# TP-DownHole-No2_Alternative.net
KiCad netlist of a schematic drawn in EAGLE
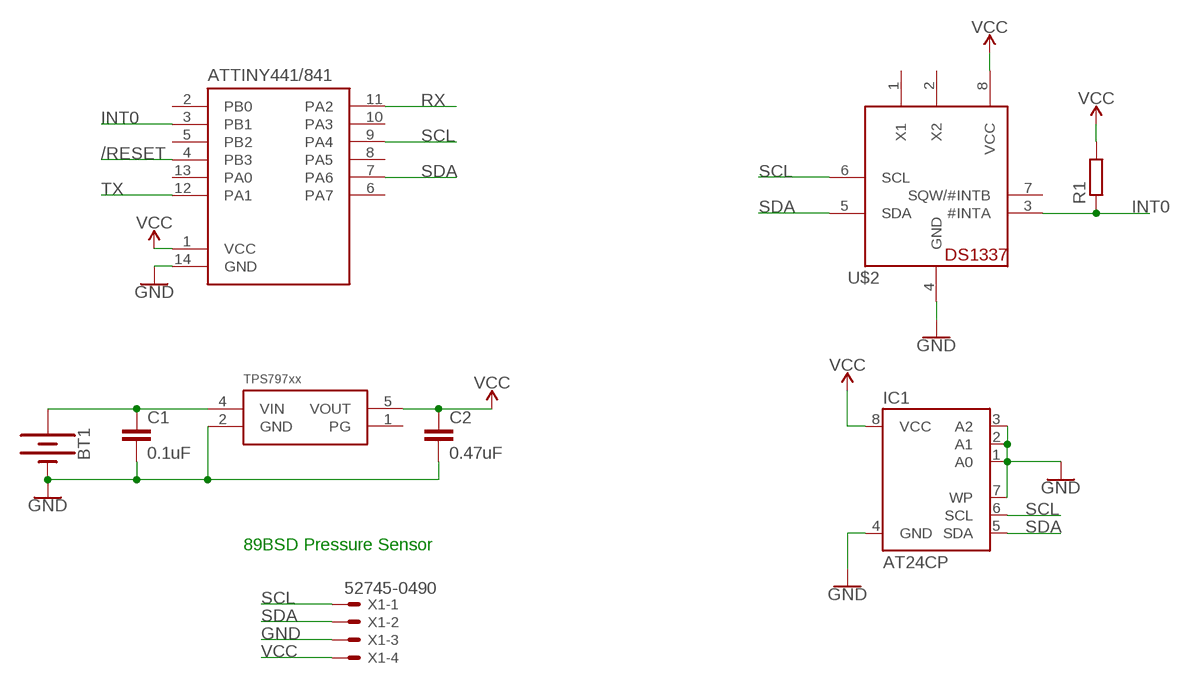
[diagram p0: schematic, sheet 1]

(export (version "E")
  (design (tool "Eeschema 10.0.6"))
  (components
    (comp (ref "BT1")
      (value "BATTERY-12MM_SMD")
      (footprint "eagle-import:BATTCON_12MM")
      (libsource (lib "eagle-import") (part "BATTERY-12MM_SMD"))
    )
    (comp (ref "C1")
      (value "0.1uF")
      (footprint "eagle-import:C0603")
      (libsource (lib "eagle-import") (part "C-EUC0603"))
    )
    (comp (ref "C2")
      (value "0.47uF")
      (footprint "eagle-import:C0603")
      (libsource (lib "eagle-import") (part "C-EUC0603"))
    )
    (comp (ref "IC1")
      (value "AT24CP")
      (footprint "eagle-import:DIL08")
      (fields (field (name "MPN") "AT24C1024BW-SH-B"))
      (libsource (lib "eagle-import") (part "AT24CP"))
    )
    (comp (ref "R1")
      (value "R-EU_R0603")
      (footprint "eagle-import:R0603")
      (libsource (lib "eagle-import") (part "R-EU_R0603"))
    )
    (comp (ref "U$1")
      (value "ATTINY441/841")
      (footprint "eagle-import:SOIC_14")
      (libsource (lib "eagle-import") (part "ATTINY441/841"))
    )
    (comp (ref "U$2")
      (value "DS1337")
      (footprint "eagle-import:DIL08-ROUND")
      (libsource (lib "eagle-import") (part "DS1337"))
    )
    (comp (ref "U$3")
      (value "TPS797XX")
      (footprint "eagle-import:DCK_R-PDSO-G5")
      (libsource (lib "eagle-import") (part "TPS797XX"))
    )
    (comp (ref "X1")
      (value "52745-0490")
      (footprint "eagle-import:52745-0490")
      (libsource (lib "eagle-import") (part "52745-0490"))
    )
  )
  (nets
    (net (code "1") (name "/INT0") (class "Default")
      (node (ref "R1") (pin "1") (pinfunction "1_1") (pintype "passive"))
      (node (ref "U$1") (pin "3") (pinfunction "PB1_3") (pintype "bidirectional"))
      (node (ref "U$2") (pin "3") (pinfunction "#INTA_3") (pintype "output"))
    )
    (net (code "2") (name "/RX") (class "Default")
      (node (ref "U$1") (pin "11") (pinfunction "PA2_11") (pintype "bidirectional"))
    )
    (net (code "3") (name "/SCL") (class "Default")
      (node (ref "IC1") (pin "6") (pinfunction "SCL_6") (pintype "bidirectional"))
      (node (ref "U$1") (pin "9") (pinfunction "PA4_9") (pintype "bidirectional"))
      (node (ref "U$2") (pin "6") (pinfunction "SCL_6") (pintype "bidirectional"))
      (node (ref "X1") (pin "1") (pinfunction "S_1") (pintype "passive"))
    )
    (net (code "4") (name "/SDA") (class "Default")
      (node (ref "IC1") (pin "5") (pinfunction "SDA_5") (pintype "bidirectional"))
      (node (ref "U$1") (pin "7") (pinfunction "PA6_7") (pintype "bidirectional"))
      (node (ref "U$2") (pin "5") (pinfunction "SDA_5") (pintype "bidirectional"))
      (node (ref "X1") (pin "2") (pinfunction "S_2") (pintype "passive"))
    )
    (net (code "5") (name "/TX") (class "Default")
      (node (ref "U$1") (pin "12") (pinfunction "PA1_12") (pintype "bidirectional"))
    )
    (net (code "6") (name "/{slash}RESET") (class "Default")
      (node (ref "U$1") (pin "4") (pinfunction "PB3_4") (pintype "bidirectional"))
    )
    (net (code "7") (name "GND") (class "Default")
      (node (ref "BT1") (pin "GND") (pinfunction "-_GND") (pintype "power_in"))
      (node (ref "C1") (pin "2") (pinfunction "2_2") (pintype "passive"))
      (node (ref "C2") (pin "2") (pinfunction "2_2") (pintype "passive"))
      (node (ref "IC1") (pin "1") (pinfunction "A0_1") (pintype "input"))
      (node (ref "IC1") (pin "2") (pinfunction "A1_2") (pintype "input"))
      (node (ref "IC1") (pin "3") (pinfunction "A2_3") (pintype "input"))
      (node (ref "IC1") (pin "4") (pinfunction "GND_4") (pintype "power_in"))
      (node (ref "IC1") (pin "7") (pinfunction "WP_7") (pintype "input"))
      (node (ref "U$1") (pin "14") (pinfunction "GND_14") (pintype "bidirectional"))
      (node (ref "U$2") (pin "4") (pinfunction "GND_4") (pintype "power_in"))
      (node (ref "U$3") (pin "2") (pinfunction "GND_2") (pintype "bidirectional"))
      (node (ref "X1") (pin "3") (pinfunction "S_3") (pintype "passive"))
    )
    (net (code "8") (name "Net-(BT1-+)") (class "Default")
      (node (ref "BT1") (pin "PWR@1") (pinfunction "+_PWR@1") (pintype "power_in"))
      (node (ref "C1") (pin "1") (pinfunction "1_1") (pintype "passive"))
      (node (ref "U$3") (pin "4") (pinfunction "VIN_4") (pintype "bidirectional"))
    )
    (net (code "9") (name "VCC") (class "Default")
      (node (ref "C2") (pin "1") (pinfunction "1_1") (pintype "passive"))
      (node (ref "IC1") (pin "8") (pinfunction "VCC_8") (pintype "power_in"))
      (node (ref "R1") (pin "2") (pinfunction "2_2") (pintype "passive"))
      (node (ref "U$1") (pin "1") (pinfunction "VCC_1") (pintype "bidirectional"))
      (node (ref "U$2") (pin "8") (pinfunction "VCC_8") (pintype "power_in"))
      (node (ref "U$3") (pin "5") (pinfunction "VOUT_5") (pintype "bidirectional"))
      (node (ref "X1") (pin "4") (pinfunction "S_4") (pintype "passive"))
    )
    (net (code "10") (name "unconnected-(U$1-PA0-Pad13)") (class "Default")
      (node (ref "U$1") (pin "13") (pinfunction "PA0_13") (pintype "bidirectional"))
    )
    (net (code "11") (name "unconnected-(U$1-PA3-Pad10)") (class "Default")
      (node (ref "U$1") (pin "10") (pinfunction "PA3_10") (pintype "bidirectional"))
    )
    (net (code "12") (name "unconnected-(U$1-PA5-Pad8)") (class "Default")
      (node (ref "U$1") (pin "8") (pinfunction "PA5_8") (pintype "bidirectional"))
    )
    (net (code "13") (name "unconnected-(U$1-PA7-Pad6)") (class "Default")
      (node (ref "U$1") (pin "6") (pinfunction "PA7_6") (pintype "bidirectional"))
    )
    (net (code "14") (name "unconnected-(U$1-PB0-Pad2)") (class "Default")
      (node (ref "U$1") (pin "2") (pinfunction "PB0_2") (pintype "bidirectional"))
    )
    (net (code "15") (name "unconnected-(U$1-PB2-Pad5)") (class "Default")
      (node (ref "U$1") (pin "5") (pinfunction "PB2_5") (pintype "bidirectional"))
    )
    (net (code "16") (name "unconnected-(U$2-SQW{slash}#INTB-Pad7)") (class "Default")
      (node (ref "U$2") (pin "7") (pinfunction "SQW/#INTB_7") (pintype "output"))
    )
    (net (code "17") (name "unconnected-(U$2-X1-Pad1)") (class "Default")
      (node (ref "U$2") (pin "1") (pinfunction "X1_1") (pintype "passive"))
    )
    (net (code "18") (name "unconnected-(U$2-X2-Pad2)") (class "Default")
      (node (ref "U$2") (pin "2") (pinfunction "X2_2") (pintype "passive"))
    )
    (net (code "19") (name "unconnected-(U$3-PG-Pad1)") (class "Default")
      (node (ref "U$3") (pin "1") (pinfunction "PG_1") (pintype "bidirectional"))
    )
  )
)
